# eBox_4G_SIM.net
KiCad netlist of a schematic drawn in Altium Designer
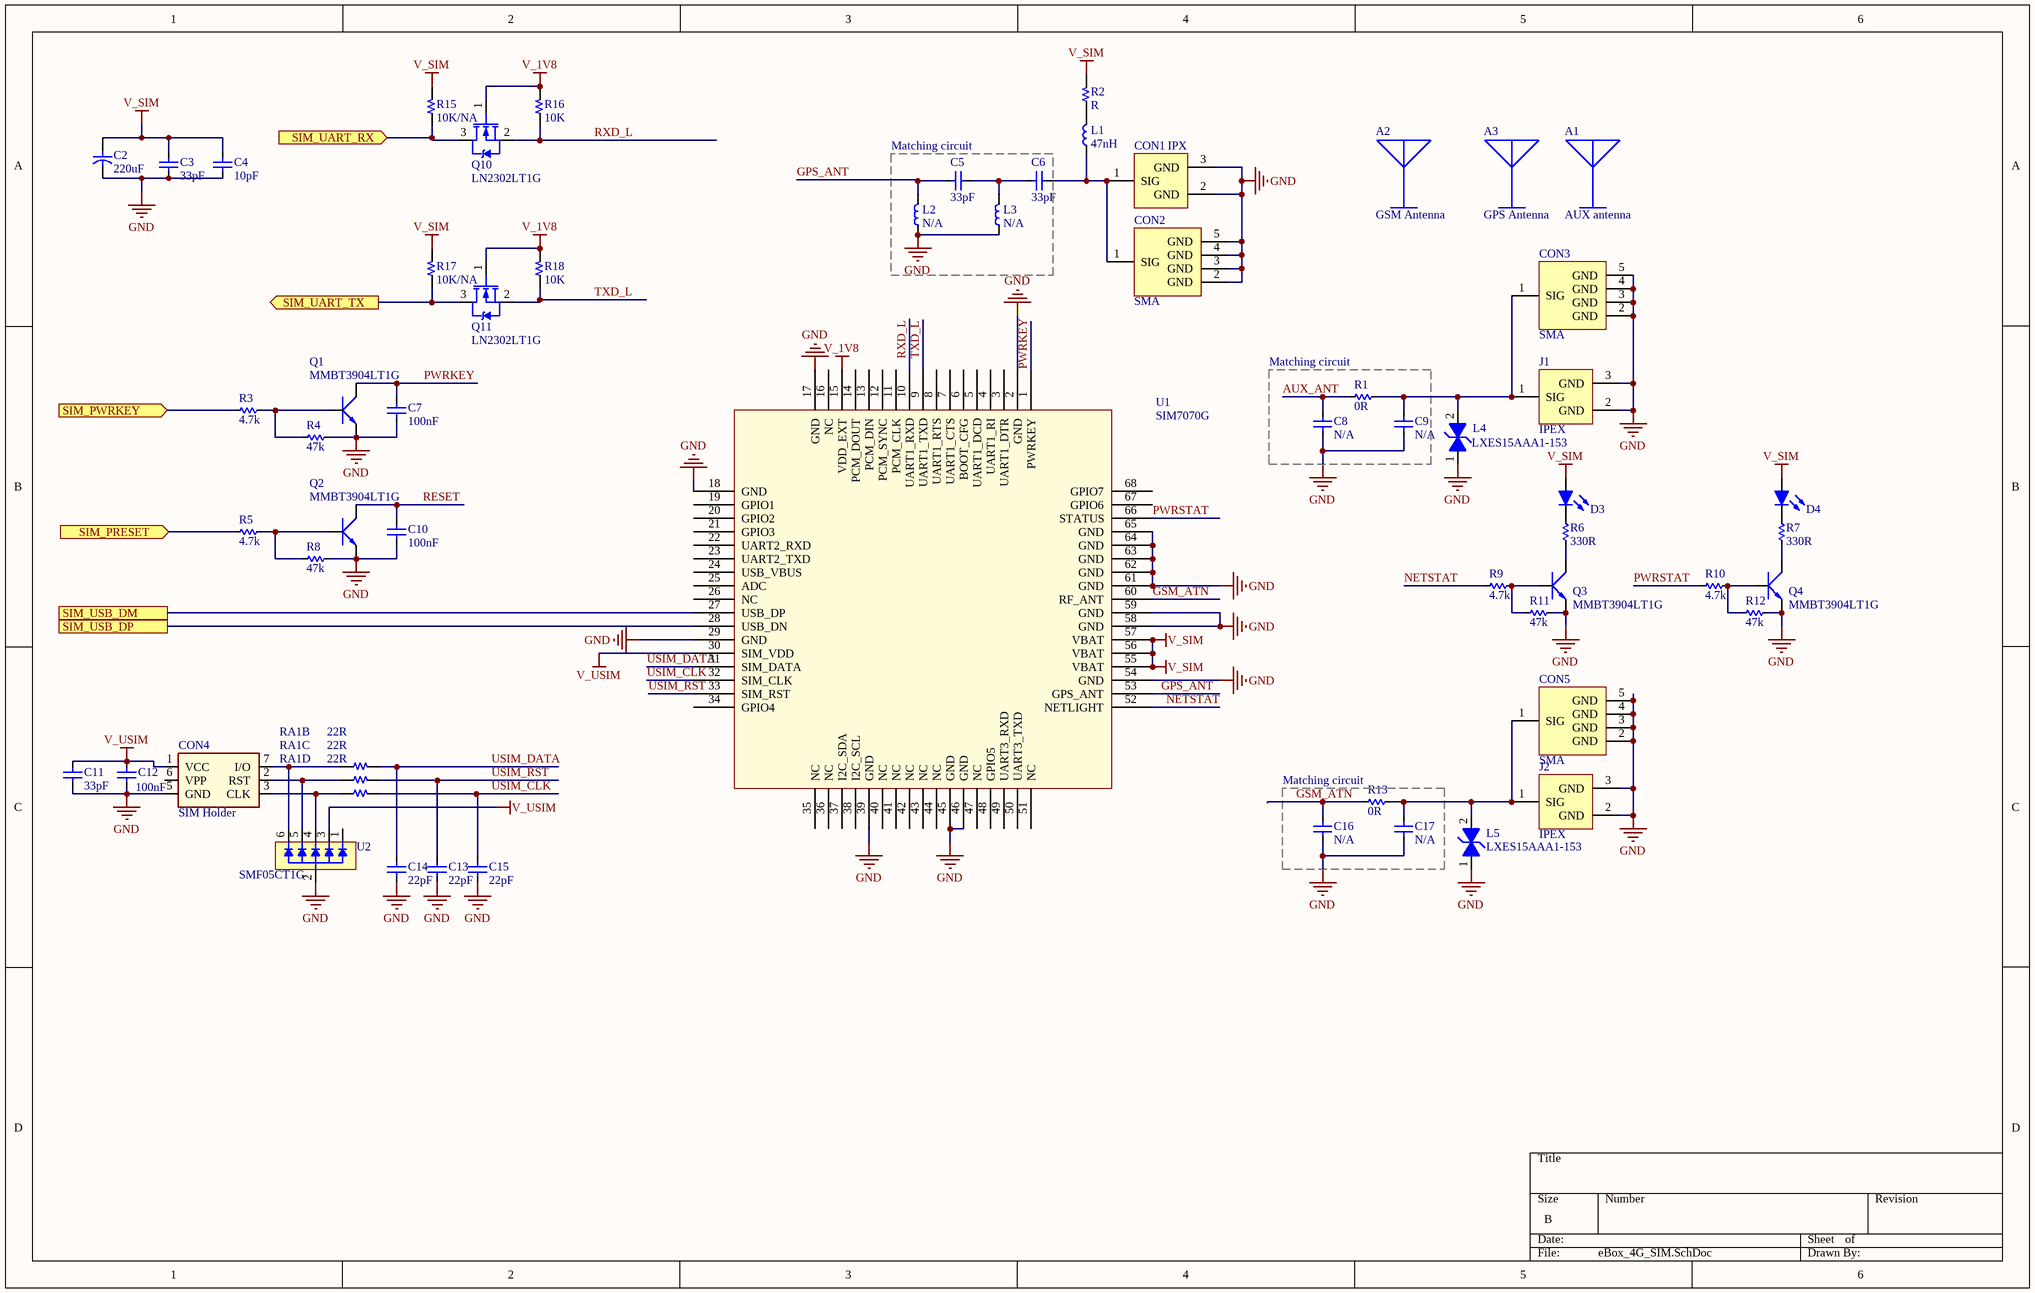
[diagram p0: eBox_4G_SIM.SchDoc]

(export (version "E")
  (design (tool "Eeschema 10.0.6"))
  (components
    (comp (ref "A1")
      (value "AUX antenna")
      (footprint "Antenna")
      (description "Antenna")
      (libsource (lib "car_logger_libs") (part "Antenna"))
    )
    (comp (ref "A2")
      (value "GSM Antenna")
      (footprint "Antenna")
      (description "Antenna")
      (libsource (lib "car_logger_libs") (part "Antenna"))
    )
    (comp (ref "A3")
      (value "GPS Antenna")
      (footprint "Antenna")
      (description "Antenna")
      (libsource (lib "car_logger_libs") (part "Antenna"))
    )
    (comp (ref "C2")
      (value "220uF")
      (footprint "C SMD ALU (D8)")
      (description "CAP TANT POLY 100UF 6.3V 1210")
      (fields
        (field (name "MANUFACTURER") "AVX Corporation")
        (field (name "MANUFACTURER PART NUMBER") "TCJB107M006R0055")
      )
      (libsource (lib "ChipFC_Lib") (part "Capacitor"))
    )
    (comp (ref "C3")
      (value "33pF")
      (footprint "CC 0603")
      (description "CAP CER 33PF 100V C0G/NP0 0603")
      (fields
        (field (name "MANUFACTURER") "Murata Electronics")
        (field (name "MANUFACTURER PART NUMBER") "GCM1885C2A330JA16D")
      )
      (libsource (lib "car_logger_libs") (part "Capacitor NP"))
    )
    (comp (ref "C4")
      (value "10pF")
      (footprint "CC 0603")
      (description "CAP CER 10PF 100V C0G/NP0 0603")
      (fields
        (field (name "MANUFACTURER") "Murata Electronics")
        (field (name "MANUFACTURER PART NUMBER") "GCM1885C2A100JA16D")
      )
      (libsource (lib "car_logger_libs") (part "Capacitor NP"))
    )
    (comp (ref "C5")
      (value "33pF")
      (footprint "CC 0603")
      (description "CAP CER 33PF 100V C0G/NP0 0603")
      (fields
        (field (name "MANUFACTURER") "Murata Electronics")
        (field (name "MANUFACTURER PART NUMBER") "GCM1885C2A330JA16D")
      )
      (libsource (lib "car_logger_libs") (part "Capacitor NP"))
    )
    (comp (ref "C6")
      (value "33pF")
      (footprint "CC 0603")
      (description "CAP CER 33PF 100V C0G/NP0 0603")
      (fields
        (field (name "MANUFACTURER") "Murata Electronics")
        (field (name "MANUFACTURER PART NUMBER") "GCM1885C2A330JA16D")
      )
      (libsource (lib "car_logger_libs") (part "Capacitor NP"))
    )
    (comp (ref "C7")
      (value "100nF")
      (footprint "CC 0603")
      (description "CAP CER 0.1UF 16V X7R 0603")
      (fields
        (field (name "MANUFACTURER") "Murata Electronics")
        (field (name "MANUFACTURER PART NUMBER") "GCJ188R71C104KA01D")
      )
      (libsource (lib "car_logger_libs") (part "Capacitor NP"))
    )
    (comp (ref "C8")
      (value "N/A")
      (footprint "CC 0603")
      (description "CAP N/A")
      (libsource (lib "car_logger_libs") (part "Capacitor NP"))
    )
    (comp (ref "C9")
      (value "N/A")
      (footprint "CC 0603")
      (description "CAP N/A")
      (libsource (lib "car_logger_libs") (part "Capacitor NP"))
    )
    (comp (ref "C10")
      (value "100nF")
      (footprint "CC 0603")
      (description "CAP CER 0.1UF 16V X7R 0603")
      (fields
        (field (name "MANUFACTURER") "Murata Electronics")
        (field (name "MANUFACTURER PART NUMBER") "GCJ188R71C104KA01D")
      )
      (libsource (lib "car_logger_libs") (part "Capacitor NP"))
    )
    (comp (ref "C11")
      (value "33pF")
      (footprint "CC 0603")
      (description "CAP CER 33PF 100V C0G/NP0 0603")
      (fields
        (field (name "MANUFACTURER") "Murata Electronics")
        (field (name "MANUFACTURER PART NUMBER") "GCM1885C2A330JA16D")
      )
      (libsource (lib "car_logger_libs") (part "Capacitor NP"))
    )
    (comp (ref "C12")
      (value "100nF")
      (footprint "CC 0603")
      (description "CAP CER 0.1UF 16V X7R 0603")
      (fields
        (field (name "MANUFACTURER") "Murata Electronics")
        (field (name "MANUFACTURER PART NUMBER") "GCJ188R71C104KA01D")
      )
      (libsource (lib "car_logger_libs") (part "Capacitor NP"))
    )
    (comp (ref "C13")
      (value "22pF")
      (footprint "CC 0603")
      (description "CAP CER 33PF 100V C0G/NP0 0603")
      (fields
        (field (name "MANUFACTURER") "Murata Electronics")
        (field (name "MANUFACTURER PART NUMBER") "GCM1885C2A330JA16D")
      )
      (libsource (lib "car_logger_libs") (part "Capacitor NP"))
    )
    (comp (ref "C14")
      (value "22pF")
      (footprint "CC 0603")
      (description "CAP CER 33PF 100V C0G/NP0 0603")
      (fields
        (field (name "MANUFACTURER") "Murata Electronics")
        (field (name "MANUFACTURER PART NUMBER") "GCM1885C2A330JA16D")
      )
      (libsource (lib "car_logger_libs") (part "Capacitor NP"))
    )
    (comp (ref "C15")
      (value "22pF")
      (footprint "CC 0603")
      (description "CAP CER 33PF 100V C0G/NP0 0603")
      (fields
        (field (name "MANUFACTURER") "Murata Electronics")
        (field (name "MANUFACTURER PART NUMBER") "GCM1885C2A330JA16D")
      )
      (libsource (lib "car_logger_libs") (part "Capacitor NP"))
    )
    (comp (ref "C16")
      (value "N/A")
      (footprint "CC 0603")
      (description "CAP N/A")
      (libsource (lib "car_logger_libs") (part "Capacitor NP"))
    )
    (comp (ref "C17")
      (value "N/A")
      (footprint "CC 0603")
      (description "CAP N/A")
      (libsource (lib "car_logger_libs") (part "Capacitor NP"))
    )
    (comp (ref "CON1")
      (value "IPX")
      (footprint "CONN/IPX/SMD")
      (libsource (lib "chipfc_altium_libs") (part "CON IPX"))
    )
    (comp (ref "CON2")
      (value "SMA")
      (footprint "CONN/SMA/RA")
      (description "SMA connectors")
      (libsource (lib "chipfc_altium_libs") (part "CON SMA"))
    )
    (comp (ref "CON3")
      (value "SMA")
      (footprint "CONN/SMA/RA")
      (description "SMA connectors")
      (libsource (lib "chipfc_altium_libs") (part "CON SMA"))
    )
    (comp (ref "CON4")
      (value "SIM Holder")
      (footprint "CON SIM Holder C707")
      (description "SIM Card holder, 6 pins")
      (libsource (lib "chipfc_altium_libs") (part "SIM holder 6 pin"))
    )
    (comp (ref "CON5")
      (value "SMA")
      (footprint "CONN/SMA/RA")
      (description "SMA connectors")
      (libsource (lib "chipfc_altium_libs") (part "CON SMA"))
    )
    (comp (ref "D3")
      (value "LED GREEN")
      (footprint "Led 0603 - green")
      (description "LED GREEN DIFFUSED 0603 SMD")
      (fields
        (field (name "MANUFACTURER") "Rohm Semiconductor")
        (field (name "MANUFACTURER PART NUMBER") "SML-D12P8WT86")
      )
      (libsource (lib "chipfc_altium_libs") (part "Led"))
    )
    (comp (ref "D4")
      (value "LED RED")
      (footprint "Led 0603 - red")
      (description "LED RED DIFFUSED 0603 SMD")
      (fields
        (field (name "MANUFACTURER") "Rohm Semiconductor")
        (field (name "MANUFACTURER PART NUMBER") "SML-D12U8WT86")
      )
      (libsource (lib "chipfc_altium_libs") (part "Led"))
    )
    (comp (ref "J1")
      (value "IPEX")
      (footprint "CONN/IPX/SMD")
      (description "CONN UMC RCPT STR 50 OHM SMD")
      (fields
        (field (name "MANUFACTURER") "Taoglas Limited")
        (field (name "MANUFACTURER PART NUMBER") "RECE.20279.001E.01")
      )
      (libsource (lib "chipfc_altium_libs") (part "CON IPX"))
    )
    (comp (ref "J2")
      (value "IPEX")
      (footprint "CONN/IPX/SMD")
      (description "CONN UMC RCPT STR 50 OHM SMD")
      (fields
        (field (name "MANUFACTURER") "Taoglas Limited")
        (field (name "MANUFACTURER PART NUMBER") "RECE.20279.001E.01")
      )
      (libsource (lib "chipfc_altium_libs") (part "CON IPX"))
    )
    (comp (ref "L1")
      (value "47nH")
      (footprint "L 0603 (1608)")
      (description "Inductor")
      (libsource (lib "chipfc_altium_libs") (part "Inductor"))
    )
    (comp (ref "L2")
      (value "N/A")
      (footprint "LL 0603")
      (description "IND N/A")
      (libsource (lib "car_logger_libs") (part "Inductor"))
    )
    (comp (ref "L3")
      (value "N/A")
      (footprint "LL 0603")
      (description "IND N/A")
      (libsource (lib "car_logger_libs") (part "Inductor"))
    )
    (comp (ref "L4")
      (value "LXES15AAA1-153")
      (footprint "C 0603")
      (description "Clamp Ipp Tvs Diode Surface Mount 1005")
      (fields (field (name "MF") "Murata") (field (name "DIGI-KEY_PART_NUMBER") "490-13210-1-ND"))
      (libsource (lib "LXES15AAA1-153") (part "LXES15AAA1-153"))
    )
    (comp (ref "L5")
      (value "LXES15AAA1-153")
      (footprint "C 0603")
      (description "Clamp Ipp Tvs Diode Surface Mount 1005")
      (fields (field (name "MF") "Murata") (field (name "DIGI-KEY_PART_NUMBER") "490-13210-1-ND"))
      (libsource (lib "LXES15AAA1-153") (part "LXES15AAA1-153"))
    )
    (comp (ref "Q1")
      (value "MMBT3904LT1G")
      (footprint "SOT-23")
      (description "TRANS NPN 40V 0.2A SOT23")
      (fields (field (name "MANUFACTURER") "ON Semiconductor"))
      (libsource (lib "car_logger_libs") (part "MMBT3904LT1G"))
    )
    (comp (ref "Q2")
      (value "MMBT3904LT1G")
      (footprint "SOT-23")
      (description "TRANS NPN 40V 0.2A SOT23")
      (fields (field (name "MANUFACTURER") "ON Semiconductor"))
      (libsource (lib "car_logger_libs") (part "MMBT3904LT1G"))
    )
    (comp (ref "Q3")
      (value "MMBT3904LT1G")
      (footprint "SOT-23")
      (description "TRANS NPN 40V 0.2A SOT23")
      (fields (field (name "MANUFACTURER") "ON Semiconductor"))
      (libsource (lib "car_logger_libs") (part "MMBT3904LT1G"))
    )
    (comp (ref "Q4")
      (value "MMBT3904LT1G")
      (footprint "SOT-23")
      (description "TRANS NPN 40V 0.2A SOT23")
      (fields (field (name "MANUFACTURER") "ON Semiconductor"))
      (libsource (lib "car_logger_libs") (part "MMBT3904LT1G"))
    )
    (comp (ref "Q10")
      (value "LN2302LT1G")
      (footprint "SOT-23")
      (description "Mosfet N")
      (libsource (lib "chipfc_altium_libs") (part "Mosfet N"))
    )
    (comp (ref "Q11")
      (value "LN2302LT1G")
      (footprint "SOT-23")
      (description "Mosfet N")
      (libsource (lib "chipfc_altium_libs") (part "Mosfet N"))
    )
    (comp (ref "R1")
      (value "0R")
      (footprint "RR 0603")
      (description "RES SMD 0 OHM JUMPER 1/10W 0603")
      (fields
        (field (name "MANUFACTURER") "Panasonic Industrial Devices")
        (field (name "MANUFACTURER PART NUMBER") "ERJ-3GEY0R00V")
      )
      (libsource (lib "car_logger_libs") (part "Resistors"))
    )
    (comp (ref "R2")
      (value "R")
      (footprint "R 0603")
      (description "Resistor")
      (libsource (lib "chipfc_altium_libs") (part "Resistor"))
    )
    (comp (ref "R3")
      (value "4.7k")
      (footprint "RR 0603")
      (description "RES SMD 4.7K OHM 1% 1/10W 0603")
      (fields
        (field (name "MANUFACTURER") "Panasonic Industrial Devices")
        (field (name "MANUFACTURER PART NUMBER") "ERJ-3EKF4701V")
      )
      (libsource (lib "car_logger_libs") (part "Resistors"))
    )
    (comp (ref "R4")
      (value "47k")
      (footprint "RR 0603")
      (description "RES SMD 47K OHM 5% 1/10W 0603")
      (fields
        (field (name "MANUFACTURER") "Panasonic Industrial Devices")
        (field (name "MANUFACTURER PART NUMBER") "ERJ-3GEYJ473V")
      )
      (libsource (lib "car_logger_libs") (part "Resistors"))
    )
    (comp (ref "R5")
      (value "4.7k")
      (footprint "RR 0603")
      (description "RES SMD 4.7K OHM 1% 1/10W 0603")
      (fields
        (field (name "MANUFACTURER") "Panasonic Industrial Devices")
        (field (name "MANUFACTURER PART NUMBER") "ERJ-3EKF4701V")
      )
      (libsource (lib "car_logger_libs") (part "Resistors"))
    )
    (comp (ref "R6")
      (value "330R")
      (footprint "RR 0603")
      (description "RES SMD 330 OHM 5% 1/10W 0603")
      (fields
        (field (name "MANUFACTURER") "Panasonic Industrial Devices")
        (field (name "MANUFACTURER PART NUMBER") "ERJ-3GEYJ331V")
      )
      (libsource (lib "car_logger_libs") (part "Resistors"))
    )
    (comp (ref "R7")
      (value "330R")
      (footprint "RR 0603")
      (description "RES SMD 330 OHM 5% 1/10W 0603")
      (fields
        (field (name "MANUFACTURER") "Panasonic Industrial Devices")
        (field (name "MANUFACTURER PART NUMBER") "ERJ-3GEYJ331V")
      )
      (libsource (lib "car_logger_libs") (part "Resistors"))
    )
    (comp (ref "R8")
      (value "47k")
      (footprint "RR 0603")
      (description "RES SMD 47K OHM 5% 1/10W 0603")
      (fields
        (field (name "MANUFACTURER") "Panasonic Industrial Devices")
        (field (name "MANUFACTURER PART NUMBER") "ERJ-3GEYJ473V")
      )
      (libsource (lib "car_logger_libs") (part "Resistors"))
    )
    (comp (ref "R9")
      (value "4.7k")
      (footprint "RR 0603")
      (description "RES SMD 4.7K OHM 1% 1/10W 0603")
      (fields
        (field (name "MANUFACTURER") "Panasonic Industrial Devices")
        (field (name "MANUFACTURER PART NUMBER") "ERJ-3EKF4701V")
      )
      (libsource (lib "car_logger_libs") (part "Resistors"))
    )
    (comp (ref "R10")
      (value "4.7k")
      (footprint "RR 0603")
      (description "RES SMD 4.7K OHM 1% 1/10W 0603")
      (fields
        (field (name "MANUFACTURER") "Panasonic Industrial Devices")
        (field (name "MANUFACTURER PART NUMBER") "ERJ-3EKF4701V")
      )
      (libsource (lib "car_logger_libs") (part "Resistors"))
    )
    (comp (ref "R11")
      (value "47k")
      (footprint "RR 0603")
      (description "RES SMD 47K OHM 5% 1/10W 0603")
      (fields
        (field (name "MANUFACTURER") "Panasonic Industrial Devices")
        (field (name "MANUFACTURER PART NUMBER") "ERJ-3GEYJ473V")
      )
      (libsource (lib "car_logger_libs") (part "Resistors"))
    )
    (comp (ref "R12")
      (value "47k")
      (footprint "RR 0603")
      (description "RES SMD 47K OHM 5% 1/10W 0603")
      (fields
        (field (name "MANUFACTURER") "Panasonic Industrial Devices")
        (field (name "MANUFACTURER PART NUMBER") "ERJ-3GEYJ473V")
      )
      (libsource (lib "car_logger_libs") (part "Resistors"))
    )
    (comp (ref "R13")
      (value "0R")
      (footprint "RR 0603")
      (description "RES SMD 0 OHM JUMPER 1/10W 0603")
      (fields
        (field (name "MANUFACTURER") "Panasonic Industrial Devices")
        (field (name "MANUFACTURER PART NUMBER") "ERJ-3GEY0R00V")
      )
      (libsource (lib "car_logger_libs") (part "Resistors"))
    )
    (comp (ref "R15")
      (value "10K/NA")
      (footprint "R 0603")
      (description "Resistor")
      (libsource (lib "chipfc_altium_libs") (part "Resistor"))
    )
    (comp (ref "R16")
      (value "10K")
      (footprint "R 0603")
      (description "Resistor")
      (libsource (lib "chipfc_altium_libs") (part "Resistor"))
    )
    (comp (ref "R17")
      (value "10K/NA")
      (footprint "R 0603")
      (description "Resistor")
      (libsource (lib "chipfc_altium_libs") (part "Resistor"))
    )
    (comp (ref "R18")
      (value "10K")
      (footprint "R 0603")
      (description "Resistor")
      (libsource (lib "chipfc_altium_libs") (part "Resistor"))
    )
    (comp (ref "RA1")
      (value "22R")
      (footprint "RAx4 1206 (3216)")
      (libsource (lib "chipfc_altium_libs") (part "Resistor Array x4"))
    )
    (comp (ref "U1") (value "SIM7070G") (footprint "SIM7070") (libsource (lib "simcom") (part "SIM7070G")))
    (comp (ref "U2")
      (value "SMF05CT1G")
      (footprint "SOT-363-6")
      (description "TVS DIODE 5V 12.5V SC88")
      (fields (field (name "MANUFACTURER") "ON Semiconductor"))
      (libsource (lib "car_logger_libs") (part "SMF05C"))
    )
  )
  (nets
    (net (code "1") (name "/AUX_ANT") (class "Default")
      (node (ref "C8") (pin "2") (pinfunction "2_2") (pintype "passive"))
      (node (ref "R1") (pin "2") (pinfunction "2_2") (pintype "passive"))
    )
    (net (code "2") (name "/GPS_ANT") (class "Default")
      (node (ref "C5") (pin "2") (pinfunction "2_2") (pintype "passive"))
      (node (ref "L2") (pin "2") (pinfunction "2_2") (pintype "passive"))
      (node (ref "U1") (pin "53") (pinfunction "GPS_ANT_53") (pintype "passive"))
    )
    (net (code "3") (name "/GSM_ATN") (class "Default")
      (node (ref "C16") (pin "2") (pinfunction "2_2") (pintype "passive"))
      (node (ref "R13") (pin "2") (pinfunction "2_2") (pintype "passive"))
      (node (ref "U1") (pin "60") (pinfunction "RF_ANT_60") (pintype "passive"))
    )
    (net (code "4") (name "/NETSTAT") (class "Default")
      (node (ref "R9") (pin "1") (pinfunction "1_1") (pintype "passive"))
      (node (ref "U1") (pin "52") (pinfunction "NETLIGHT_52") (pintype "passive"))
    )
    (net (code "5") (name "/PWRKEY") (class "Default")
      (node (ref "C7") (pin "1") (pinfunction "1_1") (pintype "passive"))
      (node (ref "Q1") (pin "3") (pinfunction "C_3") (pintype "passive"))
      (node (ref "U1") (pin "1") (pinfunction "PWRKEY_1") (pintype "passive"))
    )
    (net (code "6") (name "/PWRSTAT") (class "Default")
      (node (ref "R10") (pin "1") (pinfunction "1_1") (pintype "passive"))
      (node (ref "U1") (pin "66") (pinfunction "STATUS_66") (pintype "passive"))
    )
    (net (code "7") (name "/RESET") (class "Default")
      (node (ref "C10") (pin "1") (pinfunction "1_1") (pintype "passive"))
      (node (ref "Q2") (pin "3") (pinfunction "C_3") (pintype "passive"))
    )
    (net (code "8") (name "/RXD_L") (class "Default")
      (node (ref "Q10") (pin "2") (pinfunction "S_2") (pintype "passive"))
      (node (ref "R16") (pin "1") (pinfunction "1_1") (pintype "passive"))
      (node (ref "U1") (pin "10") (pinfunction "UART1_RXD_10") (pintype "passive"))
    )
    (net (code "9") (name "/SIM_PRESET") (class "Default")
      (node (ref "R5") (pin "1") (pinfunction "1_1") (pintype "passive"))
    )
    (net (code "10") (name "/SIM_PWRKEY") (class "Default")
      (node (ref "R3") (pin "1") (pinfunction "1_1") (pintype "passive"))
    )
    (net (code "11") (name "/SIM_UART_RX") (class "Default")
      (node (ref "Q10") (pin "3") (pinfunction "D_3") (pintype "passive"))
      (node (ref "R15") (pin "1") (pinfunction "1_1") (pintype "passive"))
    )
    (net (code "12") (name "/SIM_UART_TX") (class "Default")
      (node (ref "Q11") (pin "3") (pinfunction "D_3") (pintype "passive"))
      (node (ref "R17") (pin "1") (pinfunction "1_1") (pintype "passive"))
    )
    (net (code "13") (name "/SIM_USB_DM") (class "Default")
      (node (ref "U1") (pin "27") (pinfunction "USB_DP_27") (pintype "passive"))
    )
    (net (code "14") (name "/SIM_USB_DP") (class "Default")
      (node (ref "U1") (pin "28") (pinfunction "USB_DN_28") (pintype "passive"))
    )
    (net (code "15") (name "/TXD_L") (class "Default")
      (node (ref "Q11") (pin "2") (pinfunction "S_2") (pintype "passive"))
      (node (ref "R18") (pin "1") (pinfunction "1_1") (pintype "passive"))
      (node (ref "U1") (pin "9") (pinfunction "UART1_TXD_9") (pintype "passive"))
    )
    (net (code "16") (name "/USIM_CLK") (class "Default")
      (node (ref "C15") (pin "1") (pinfunction "1_1") (pintype "passive"))
      (node (ref "RA1") (pin "5") (pinfunction "5_5") (pintype "passive"))
      (node (ref "U1") (pin "32") (pinfunction "SIM_CLK_32") (pintype "passive"))
    )
    (net (code "17") (name "/USIM_DATA") (class "Default")
      (node (ref "C14") (pin "1") (pinfunction "1_1") (pintype "passive"))
      (node (ref "RA1") (pin "7") (pinfunction "7_7") (pintype "passive"))
      (node (ref "U1") (pin "31") (pinfunction "SIM_DATA_31") (pintype "passive"))
    )
    (net (code "18") (name "/USIM_RST") (class "Default")
      (node (ref "C13") (pin "1") (pinfunction "1_1") (pintype "passive"))
      (node (ref "RA1") (pin "6") (pinfunction "6_6") (pintype "passive"))
      (node (ref "U1") (pin "33") (pinfunction "SIM_RST_33") (pintype "passive"))
    )
    (net (code "19") (name "GND") (class "Default")
      (node (ref "C10") (pin "2") (pinfunction "2_2") (pintype "passive"))
      (node (ref "C11") (pin "2") (pinfunction "2_2") (pintype "passive"))
      (node (ref "C12") (pin "2") (pinfunction "2_2") (pintype "passive"))
      (node (ref "C13") (pin "2") (pinfunction "2_2") (pintype "passive"))
      (node (ref "C14") (pin "2") (pinfunction "2_2") (pintype "passive"))
      (node (ref "C15") (pin "2") (pinfunction "2_2") (pintype "passive"))
      (node (ref "C16") (pin "1") (pinfunction "1_1") (pintype "passive"))
      (node (ref "C17") (pin "1") (pinfunction "1_1") (pintype "passive"))
      (node (ref "C2") (pin "2") (pinfunction "2_2") (pintype "passive"))
      (node (ref "C3") (pin "1") (pinfunction "1_1") (pintype "passive"))
      (node (ref "C4") (pin "1") (pinfunction "1_1") (pintype "passive"))
      (node (ref "C7") (pin "2") (pinfunction "2_2") (pintype "passive"))
      (node (ref "C8") (pin "1") (pinfunction "1_1") (pintype "passive"))
      (node (ref "C9") (pin "1") (pinfunction "1_1") (pintype "passive"))
      (node (ref "CON1") (pin "2") (pinfunction "GND_2") (pintype "passive"))
      (node (ref "CON1") (pin "3") (pinfunction "GND_3") (pintype "passive"))
      (node (ref "CON2") (pin "2") (pinfunction "GND_2") (pintype "passive"))
      (node (ref "CON2") (pin "3") (pinfunction "GND_3") (pintype "passive"))
      (node (ref "CON2") (pin "4") (pinfunction "GND_4") (pintype "passive"))
      (node (ref "CON2") (pin "5") (pinfunction "GND_5") (pintype "passive"))
      (node (ref "CON3") (pin "2") (pinfunction "GND_2") (pintype "passive"))
      (node (ref "CON3") (pin "3") (pinfunction "GND_3") (pintype "passive"))
      (node (ref "CON3") (pin "4") (pinfunction "GND_4") (pintype "passive"))
      (node (ref "CON3") (pin "5") (pinfunction "GND_5") (pintype "passive"))
      (node (ref "CON4") (pin "5") (pinfunction "GND_5") (pintype "power_in"))
      (node (ref "CON5") (pin "2") (pinfunction "GND_2") (pintype "passive"))
      (node (ref "CON5") (pin "3") (pinfunction "GND_3") (pintype "passive"))
      (node (ref "CON5") (pin "4") (pinfunction "GND_4") (pintype "passive"))
      (node (ref "CON5") (pin "5") (pinfunction "GND_5") (pintype "passive"))
      (node (ref "J1") (pin "2") (pinfunction "GND_2") (pintype "passive"))
      (node (ref "J1") (pin "3") (pinfunction "GND_3") (pintype "passive"))
      (node (ref "J2") (pin "2") (pinfunction "GND_2") (pintype "passive"))
      (node (ref "J2") (pin "3") (pinfunction "GND_3") (pintype "passive"))
      (node (ref "L2") (pin "1") (pinfunction "1_1") (pintype "passive"))
      (node (ref "L3") (pin "1") (pinfunction "1_1") (pintype "passive"))
      (node (ref "L4") (pin "1") (pinfunction "1_1") (pintype "passive"))
      (node (ref "L5") (pin "1") (pinfunction "1_1") (pintype "passive"))
      (node (ref "Q1") (pin "2") (pinfunction "E_2") (pintype "passive"))
      (node (ref "Q2") (pin "2") (pinfunction "E_2") (pintype "passive"))
      (node (ref "Q3") (pin "2") (pinfunction "E_2") (pintype "passive"))
      (node (ref "Q4") (pin "2") (pinfunction "E_2") (pintype "passive"))
      (node (ref "R11") (pin "2") (pinfunction "2_2") (pintype "passive"))
      (node (ref "R12") (pin "2") (pinfunction "2_2") (pintype "passive"))
      (node (ref "R4") (pin "2") (pinfunction "2_2") (pintype "passive"))
      (node (ref "R8") (pin "2") (pinfunction "2_2") (pintype "passive"))
      (node (ref "U1") (pin "17") (pinfunction "GND_17") (pintype "passive"))
      (node (ref "U1") (pin "18") (pinfunction "GND_18") (pintype "passive"))
      (node (ref "U1") (pin "2") (pinfunction "GND_2") (pintype "passive"))
      (node (ref "U1") (pin "29") (pinfunction "GND_29") (pintype "passive"))
      (node (ref "U1") (pin "39") (pinfunction "GND_39") (pintype "passive"))
      (node (ref "U1") (pin "45") (pinfunction "GND_45") (pintype "passive"))
      (node (ref "U1") (pin "46") (pinfunction "GND_46") (pintype "passive"))
      (node (ref "U1") (pin "54") (pinfunction "GND_54") (pintype "passive"))
      (node (ref "U1") (pin "58") (pinfunction "GND_58") (pintype "passive"))
      (node (ref "U1") (pin "59") (pinfunction "GND_59") (pintype "passive"))
      (node (ref "U1") (pin "61") (pinfunction "GND_61") (pintype "passive"))
      (node (ref "U1") (pin "62") (pinfunction "GND_62") (pintype "passive"))
      (node (ref "U1") (pin "63") (pinfunction "GND_63") (pintype "passive"))
      (node (ref "U1") (pin "64") (pinfunction "GND_64") (pintype "passive"))
      (node (ref "U1") (pin "65") (pinfunction "GND_65") (pintype "passive"))
      (node (ref "U2") (pin "2") (pinfunction "A_2") (pintype "passive"))
    )
    (net (code "20") (name "Net-(C5-Pad1)") (class "Default")
      (node (ref "C5") (pin "1") (pinfunction "1_1") (pintype "passive"))
      (node (ref "C6") (pin "2") (pinfunction "2_2") (pintype "passive"))
      (node (ref "L3") (pin "2") (pinfunction "2_2") (pintype "passive"))
    )
    (net (code "21") (name "Net-(CON1-SIG)") (class "Default")
      (node (ref "C6") (pin "1") (pinfunction "1_1") (pintype "passive"))
      (node (ref "CON1") (pin "1") (pinfunction "SIG_1") (pintype "passive"))
      (node (ref "CON2") (pin "1") (pinfunction "SIG_1") (pintype "passive"))
      (node (ref "L1") (pin "1") (pinfunction "1_1") (pintype "passive"))
    )
    (net (code "22") (name "Net-(CON3-SIG)") (class "Default")
      (node (ref "C9") (pin "2") (pinfunction "2_2") (pintype "passive"))
      (node (ref "CON3") (pin "1") (pinfunction "SIG_1") (pintype "passive"))
      (node (ref "J1") (pin "1") (pinfunction "SIG_1") (pintype "passive"))
      (node (ref "L4") (pin "2") (pinfunction "2_2") (pintype "passive"))
      (node (ref "R1") (pin "1") (pinfunction "1_1") (pintype "passive"))
    )
    (net (code "23") (name "Net-(CON4-CLK)") (class "Default")
      (node (ref "CON4") (pin "3") (pinfunction "CLK_3") (pintype "passive"))
      (node (ref "RA1") (pin "4") (pinfunction "4_4") (pintype "passive"))
      (node (ref "U2") (pin "4") (pinfunction "K4_4") (pintype "passive"))
    )
    (net (code "24") (name "Net-(CON4-I{slash}O)") (class "Default")
      (node (ref "CON4") (pin "7") (pinfunction "I/O_7") (pintype "passive"))
      (node (ref "RA1") (pin "2") (pinfunction "2_2") (pintype "passive"))
      (node (ref "U2") (pin "6") (pinfunction "K6_6") (pintype "passive"))
    )
    (net (code "25") (name "Net-(CON4-RST)") (class "Default")
      (node (ref "CON4") (pin "2") (pinfunction "RST_2") (pintype "passive"))
      (node (ref "RA1") (pin "3") (pinfunction "3_3") (pintype "passive"))
      (node (ref "U2") (pin "5") (pinfunction "K5_5") (pintype "passive"))
    )
    (net (code "26") (name "Net-(CON5-SIG)") (class "Default")
      (node (ref "C17") (pin "2") (pinfunction "2_2") (pintype "passive"))
      (node (ref "CON5") (pin "1") (pinfunction "SIG_1") (pintype "passive"))
      (node (ref "J2") (pin "1") (pinfunction "SIG_1") (pintype "passive"))
      (node (ref "L5") (pin "2") (pinfunction "2_2") (pintype "passive"))
      (node (ref "R13") (pin "1") (pinfunction "1_1") (pintype "passive"))
    )
    (net (code "27") (name "Net-(D3-K)") (class "Default")
      (node (ref "D3") (pin "2") (pinfunction "K_2") (pintype "passive"))
      (node (ref "R6") (pin "2") (pinfunction "2_2") (pintype "passive"))
    )
    (net (code "28") (name "Net-(D4-K)") (class "Default")
      (node (ref "D4") (pin "2") (pinfunction "K_2") (pintype "passive"))
      (node (ref "R7") (pin "2") (pinfunction "2_2") (pintype "passive"))
    )
    (net (code "29") (name "Net-(L1-Pad2)") (class "Default")
      (node (ref "L1") (pin "2") (pinfunction "2_2") (pintype "passive"))
      (node (ref "R2") (pin "1") (pinfunction "1_1") (pintype "passive"))
    )
    (net (code "30") (name "Net-(Q1-B)") (class "Default")
      (node (ref "Q1") (pin "1") (pinfunction "B_1") (pintype "passive"))
      (node (ref "R3") (pin "2") (pinfunction "2_2") (pintype "passive"))
      (node (ref "R4") (pin "1") (pinfunction "1_1") (pintype "passive"))
    )
    (net (code "31") (name "Net-(Q2-B)") (class "Default")
      (node (ref "Q2") (pin "1") (pinfunction "B_1") (pintype "passive"))
      (node (ref "R5") (pin "2") (pinfunction "2_2") (pintype "passive"))
      (node (ref "R8") (pin "1") (pinfunction "1_1") (pintype "passive"))
    )
    (net (code "32") (name "Net-(Q3-B)") (class "Default")
      (node (ref "Q3") (pin "1") (pinfunction "B_1") (pintype "passive"))
      (node (ref "R11") (pin "1") (pinfunction "1_1") (pintype "passive"))
      (node (ref "R9") (pin "2") (pinfunction "2_2") (pintype "passive"))
    )
    (net (code "33") (name "Net-(Q3-C)") (class "Default")
      (node (ref "Q3") (pin "3") (pinfunction "C_3") (pintype "passive"))
      (node (ref "R6") (pin "1") (pinfunction "1_1") (pintype "passive"))
    )
    (net (code "34") (name "Net-(Q4-B)") (class "Default")
      (node (ref "Q4") (pin "1") (pinfunction "B_1") (pintype "passive"))
      (node (ref "R10") (pin "2") (pinfunction "2_2") (pintype "passive"))
      (node (ref "R12") (pin "1") (pinfunction "1_1") (pintype "passive"))
    )
    (net (code "35") (name "Net-(Q4-C)") (class "Default")
      (node (ref "Q4") (pin "3") (pinfunction "C_3") (pintype "passive"))
      (node (ref "R7") (pin "1") (pinfunction "1_1") (pintype "passive"))
    )
    (net (code "36") (name "V_1V8") (class "Default")
      (node (ref "Q10") (pin "1") (pinfunction "G_1") (pintype "passive"))
      (node (ref "Q11") (pin "1") (pinfunction "G_1") (pintype "passive"))
      (node (ref "R16") (pin "2") (pinfunction "2_2") (pintype "passive"))
      (node (ref "R18") (pin "2") (pinfunction "2_2") (pintype "passive"))
      (node (ref "U1") (pin "15") (pinfunction "VDD_EXT_15") (pintype "passive"))
    )
    (net (code "37") (name "V_SIM") (class "Default")
      (node (ref "C2") (pin "1") (pinfunction "1_1") (pintype "passive"))
      (node (ref "C3") (pin "2") (pinfunction "2_2") (pintype "passive"))
      (node (ref "C4") (pin "2") (pinfunction "2_2") (pintype "passive"))
      (node (ref "D3") (pin "1") (pinfunction "A_1") (pintype "passive"))
      (node (ref "D4") (pin "1") (pinfunction "A_1") (pintype "passive"))
      (node (ref "R15") (pin "2") (pinfunction "2_2") (pintype "passive"))
      (node (ref "R17") (pin "2") (pinfunction "2_2") (pintype "passive"))
      (node (ref "R2") (pin "2") (pinfunction "2_2") (pintype "passive"))
      (node (ref "U1") (pin "55") (pinfunction "VBAT_55") (pintype "passive"))
      (node (ref "U1") (pin "56") (pinfunction "VBAT_56") (pintype "passive"))
      (node (ref "U1") (pin "57") (pinfunction "VBAT_57") (pintype "passive"))
    )
    (net (code "38") (name "V_USIM") (class "Default")
      (node (ref "C11") (pin "1") (pinfunction "1_1") (pintype "passive"))
      (node (ref "C12") (pin "1") (pinfunction "1_1") (pintype "passive"))
      (node (ref "CON4") (pin "1") (pinfunction "VCC_1") (pintype "power_in"))
      (node (ref "U1") (pin "30") (pinfunction "SIM_VDD_30") (pintype "passive"))
      (node (ref "U2") (pin "3") (pinfunction "K3_3") (pintype "passive"))
    )
    (net (code "39") (name "unconnected-(CON4-VPP-Pad6)") (class "Default")
      (node (ref "CON4") (pin "6") (pinfunction "VPP_6") (pintype "passive"))
    )
    (net (code "40") (name "unconnected-(U1-ADC-Pad25)") (class "Default")
      (node (ref "U1") (pin "25") (pinfunction "ADC_25") (pintype "passive"))
    )
    (net (code "41") (name "unconnected-(U1-BOOT_CFG-Pad6)") (class "Default")
      (node (ref "U1") (pin "6") (pinfunction "BOOT_CFG_6") (pintype "passive"))
    )
    (net (code "42") (name "unconnected-(U1-GPIO1-Pad19)") (class "Default")
      (node (ref "U1") (pin "19") (pinfunction "GPIO1_19") (pintype "passive"))
    )
    (net (code "43") (name "unconnected-(U1-GPIO2-Pad20)") (class "Default")
      (node (ref "U1") (pin "20") (pinfunction "GPIO2_20") (pintype "passive"))
    )
    (net (code "44") (name "unconnected-(U1-GPIO3-Pad21)") (class "Default")
      (node (ref "U1") (pin "21") (pinfunction "GPIO3_21") (pintype "passive"))
    )
    (net (code "45") (name "unconnected-(U1-GPIO4-Pad34)") (class "Default")
      (node (ref "U1") (pin "34") (pinfunction "GPIO4_34") (pintype "passive"))
    )
    (net (code "46") (name "unconnected-(U1-GPIO5-Pad48)") (class "Default")
      (node (ref "U1") (pin "48") (pinfunction "GPIO5_48") (pintype "passive"))
    )
    (net (code "47") (name "unconnected-(U1-GPIO6-Pad67)") (class "Default")
      (node (ref "U1") (pin "67") (pinfunction "GPIO6_67") (pintype "passive"))
    )
    (net (code "48") (name "unconnected-(U1-GPIO7-Pad68)") (class "Default")
      (node (ref "U1") (pin "68") (pinfunction "GPIO7_68") (pintype "passive"))
    )
    (net (code "49") (name "unconnected-(U1-I2C_SCL-Pad38)") (class "Default")
      (node (ref "U1") (pin "38") (pinfunction "I2C_SCL_38") (pintype "passive"))
    )
    (net (code "50") (name "unconnected-(U1-I2C_SDA-Pad37)") (class "Default")
      (node (ref "U1") (pin "37") (pinfunction "I2C_SDA_37") (pintype "passive"))
    )
    (net (code "51") (name "unconnected-(U1-NC-Pad16)") (class "Default")
      (node (ref "U1") (pin "16") (pinfunction "NC_16") (pintype "passive"))
    )
    (net (code "52") (name "unconnected-(U1-NC-Pad26)") (class "Default")
      (node (ref "U1") (pin "26") (pinfunction "NC_26") (pintype "passive"))
    )
    (net (code "53") (name "unconnected-(U1-NC-Pad35)") (class "Default")
      (node (ref "U1") (pin "35") (pinfunction "NC_35") (pintype "passive"))
    )
    (net (code "54") (name "unconnected-(U1-NC-Pad36)") (class "Default")
      (node (ref "U1") (pin "36") (pinfunction "NC_36") (pintype "passive"))
    )
    (net (code "55") (name "unconnected-(U1-NC-Pad40)") (class "Default")
      (node (ref "U1") (pin "40") (pinfunction "NC_40") (pintype "passive"))
    )
    (net (code "56") (name "unconnected-(U1-NC-Pad41)") (class "Default")
      (node (ref "U1") (pin "41") (pinfunction "NC_41") (pintype "passive"))
    )
    (net (code "57") (name "unconnected-(U1-NC-Pad42)") (class "Default")
      (node (ref "U1") (pin "42") (pinfunction "NC_42") (pintype "passive"))
    )
    (net (code "58") (name "unconnected-(U1-NC-Pad43)") (class "Default")
      (node (ref "U1") (pin "43") (pinfunction "NC_43") (pintype "passive"))
    )
    (net (code "59") (name "unconnected-(U1-NC-Pad44)") (class "Default")
      (node (ref "U1") (pin "44") (pinfunction "NC_44") (pintype "passive"))
    )
    (net (code "60") (name "unconnected-(U1-NC-Pad47)") (class "Default")
      (node (ref "U1") (pin "47") (pinfunction "NC_47") (pintype "passive"))
    )
    (net (code "61") (name "unconnected-(U1-NC-Pad51)") (class "Default")
      (node (ref "U1") (pin "51") (pinfunction "NC_51") (pintype "passive"))
    )
    (net (code "62") (name "unconnected-(U1-PCM_CLK-Pad11)") (class "Default")
      (node (ref "U1") (pin "11") (pinfunction "PCM_CLK_11") (pintype "passive"))
    )
    (net (code "63") (name "unconnected-(U1-PCM_DIN-Pad13)") (class "Default")
      (node (ref "U1") (pin "13") (pinfunction "PCM_DIN_13") (pintype "passive"))
    )
    (net (code "64") (name "unconnected-(U1-PCM_DOUT-Pad14)") (class "Default")
      (node (ref "U1") (pin "14") (pinfunction "PCM_DOUT_14") (pintype "passive"))
    )
    (net (code "65") (name "unconnected-(U1-PCM_SYNC-Pad12)") (class "Default")
      (node (ref "U1") (pin "12") (pinfunction "PCM_SYNC_12") (pintype "passive"))
    )
    (net (code "66") (name "unconnected-(U1-UART1_CTS-Pad7)") (class "Default")
      (node (ref "U1") (pin "7") (pinfunction "UART1_CTS_7") (pintype "passive"))
    )
    (net (code "67") (name "unconnected-(U1-UART1_DCD-Pad5)") (class "Default")
      (node (ref "U1") (pin "5") (pinfunction "UART1_DCD_5") (pintype "passive"))
    )
    (net (code "68") (name "unconnected-(U1-UART1_DTR-Pad3)") (class "Default")
      (node (ref "U1") (pin "3") (pinfunction "UART1_DTR_3") (pintype "passive"))
    )
    (net (code "69") (name "unconnected-(U1-UART1_RI-Pad4)") (class "Default")
      (node (ref "U1") (pin "4") (pinfunction "UART1_RI_4") (pintype "passive"))
    )
    (net (code "70") (name "unconnected-(U1-UART1_RTS-Pad8)") (class "Default")
      (node (ref "U1") (pin "8") (pinfunction "UART1_RTS_8") (pintype "passive"))
    )
    (net (code "71") (name "unconnected-(U1-UART2_RXD-Pad22)") (class "Default")
      (node (ref "U1") (pin "22") (pinfunction "UART2_RXD_22") (pintype "passive"))
    )
    (net (code "72") (name "unconnected-(U1-UART2_TXD-Pad23)") (class "Default")
      (node (ref "U1") (pin "23") (pinfunction "UART2_TXD_23") (pintype "passive"))
    )
    (net (code "73") (name "unconnected-(U1-UART3_RXD-Pad49)") (class "Default")
      (node (ref "U1") (pin "49") (pinfunction "UART3_RXD_49") (pintype "passive"))
    )
    (net (code "74") (name "unconnected-(U1-UART3_TXD-Pad50)") (class "Default")
      (node (ref "U1") (pin "50") (pinfunction "UART3_TXD_50") (pintype "passive"))
    )
    (net (code "75") (name "unconnected-(U1-USB_VBUS-Pad24)") (class "Default")
      (node (ref "U1") (pin "24") (pinfunction "USB_VBUS_24") (pintype "passive"))
    )
    (net (code "76") (name "unconnected-(U2-K1-Pad1)") (class "Default")
      (node (ref "U2") (pin "1") (pinfunction "K1_1") (pintype "passive"))
    )
  )
)
